# Vers_6_Moppy_Board.net
KiCad netlist of a schematic drawn in EAGLE
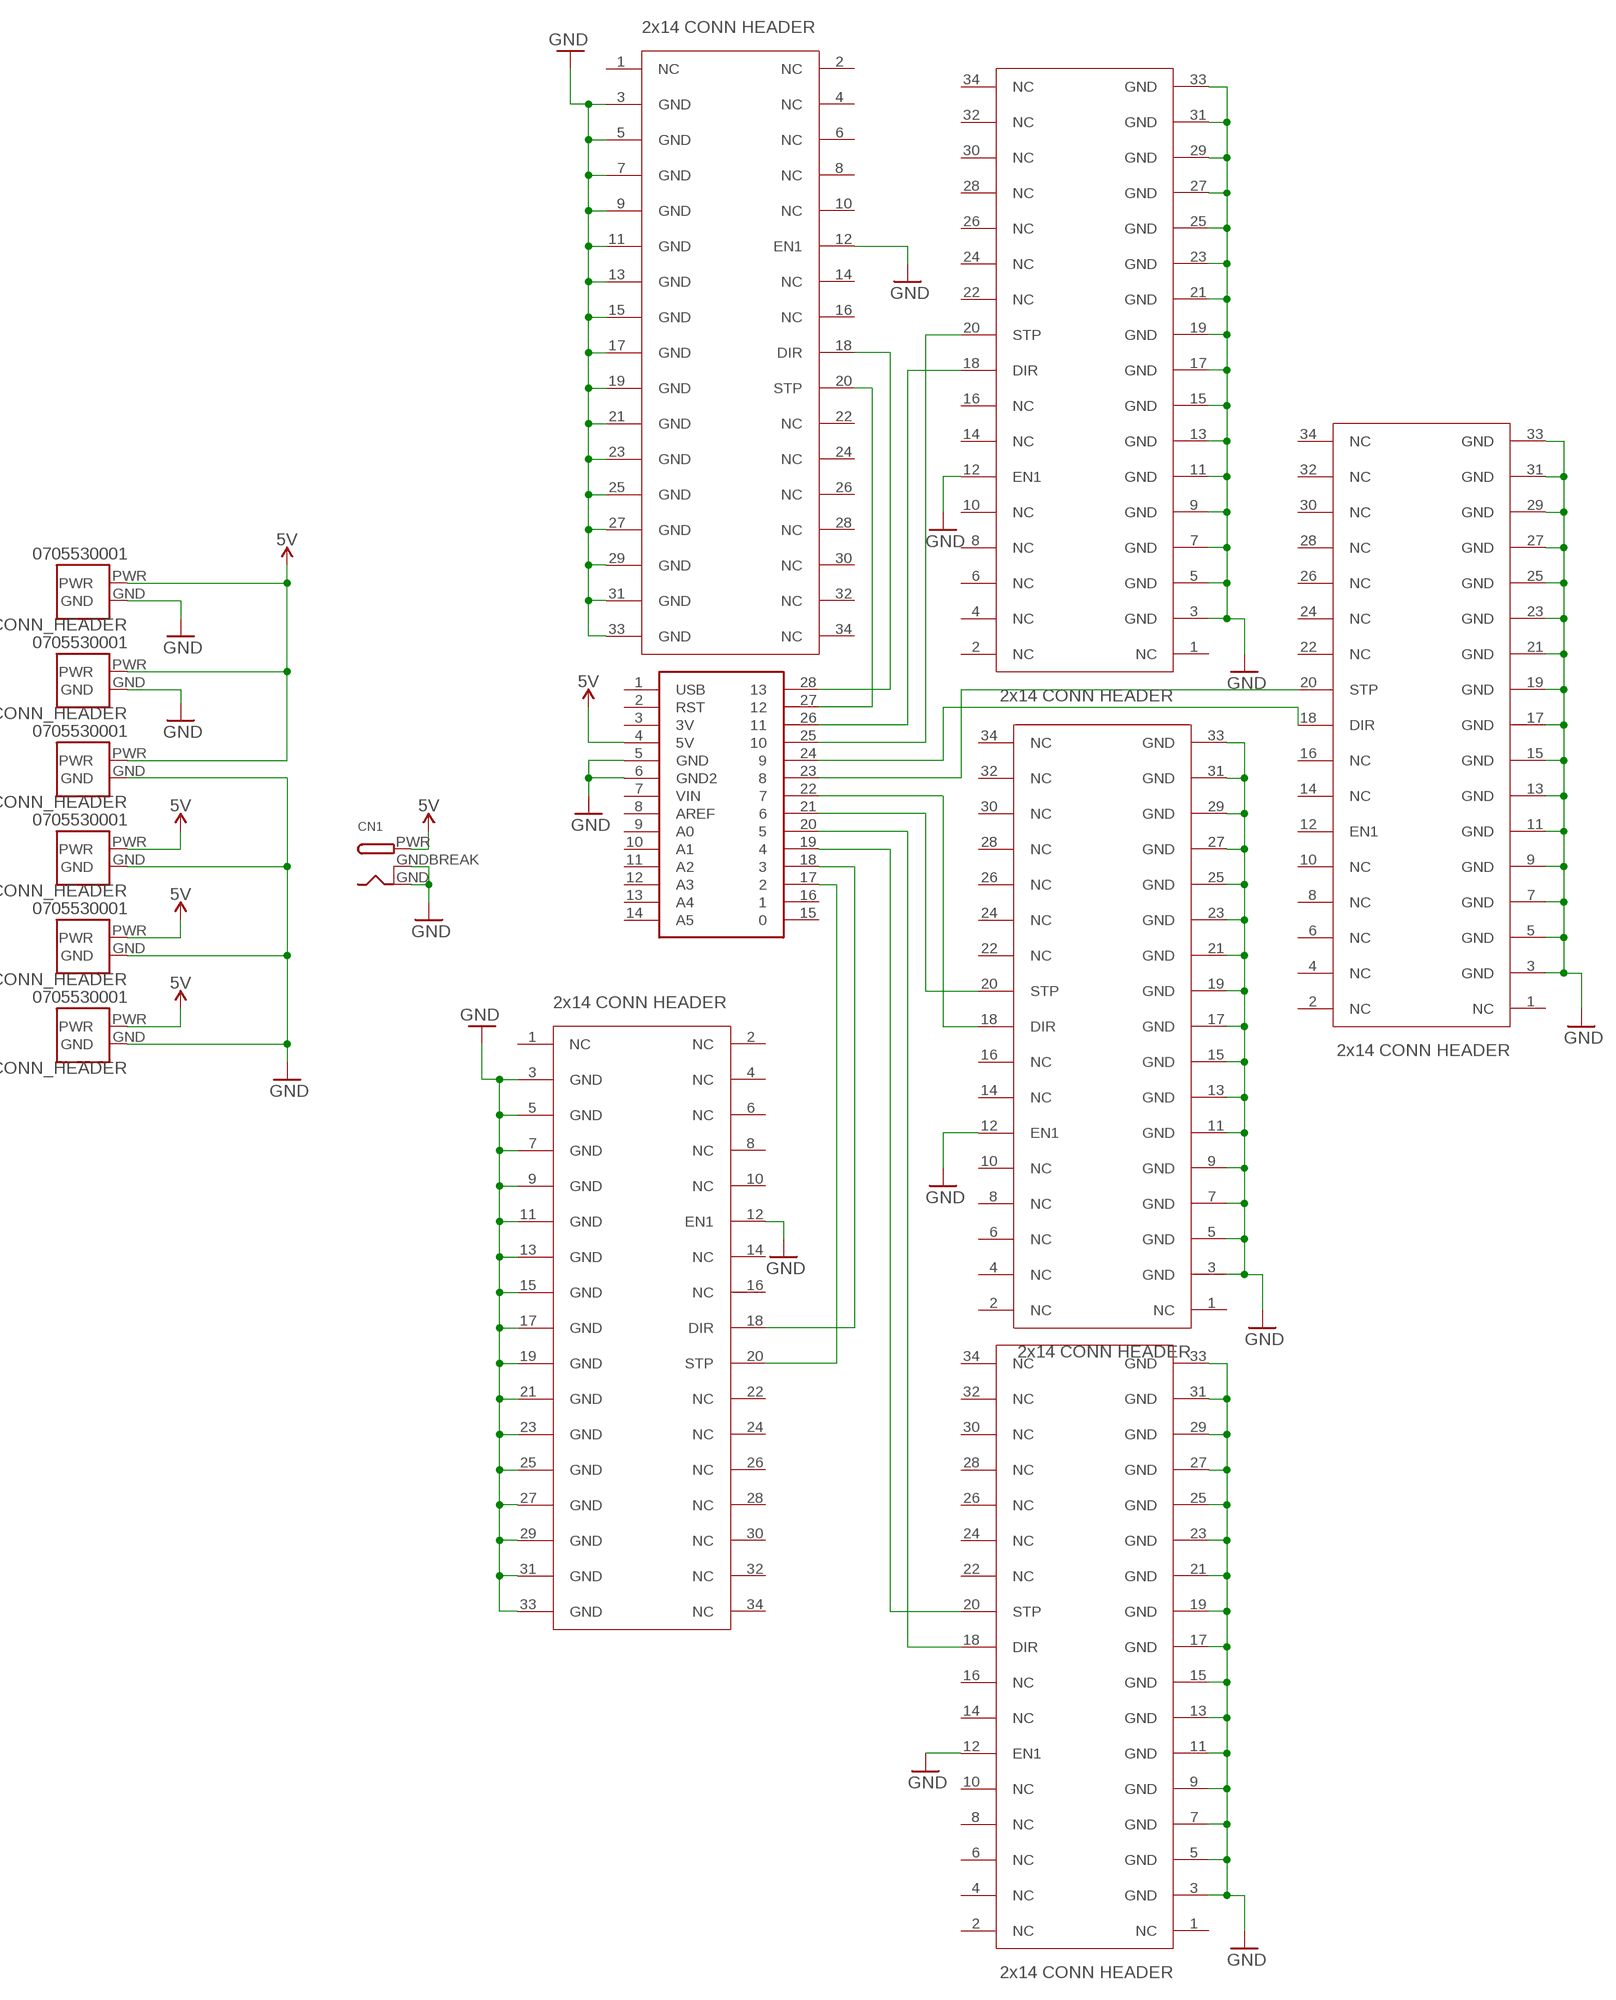
[diagram p0: schematic, sheet 1]

(export (version "E")
  (design (tool "Eeschema 10.0.6"))
  (components
    (comp (ref "CN1")
      (value "DCBARRELPTH")
      (footprint "eagle-import:DCJACK_2MM_PTH")
      (libsource (lib "eagle-import") (part "DCBARRELPTH"))
    )
    (comp (ref "U$1")
      (value "2X14_CONN_HEADER")
      (footprint "eagle-import:2X17_CONN_HEADER")
      (libsource (lib "eagle-import") (part "2X14_CONN_HEADER"))
    )
    (comp (ref "U$2")
      (value "2X14_CONN_HEADER")
      (footprint "eagle-import:2X17_CONN_HEADER")
      (libsource (lib "eagle-import") (part "2X14_CONN_HEADER"))
    )
    (comp (ref "U$3")
      (value "2X14_CONN_HEADER")
      (footprint "eagle-import:2X17_CONN_HEADER")
      (libsource (lib "eagle-import") (part "2X14_CONN_HEADER"))
    )
    (comp (ref "U$4")
      (value "2X14_CONN_HEADER")
      (footprint "eagle-import:2X17_CONN_HEADER")
      (libsource (lib "eagle-import") (part "2X14_CONN_HEADER"))
    )
    (comp (ref "U$5")
      (value "2X14_CONN_HEADER")
      (footprint "eagle-import:2X17_CONN_HEADER")
      (libsource (lib "eagle-import") (part "2X14_CONN_HEADER"))
    )
    (comp (ref "U$6")
      (value "2X14_CONN_HEADER")
      (footprint "eagle-import:2X17_CONN_HEADER")
      (libsource (lib "eagle-import") (part "2X14_CONN_HEADER"))
    )
    (comp (ref "U$8")
      (value "METROMINI")
      (footprint "eagle-import:METROMINI")
      (libsource (lib "eagle-import") (part "METROMINI"))
    )
    (comp (ref "X1")
      (value "0705530001")
      (footprint "eagle-import:MOLEX_0705530001")
      (fields (field (name "DIGI-KEY_PART_NUMBER") "WM4900-ND") (field (name "MF") "Molex"))
      (libsource (lib "eagle-import") (part "0705530001"))
    )
    (comp (ref "X2")
      (value "0705530001")
      (footprint "eagle-import:MOLEX_0705530001")
      (fields (field (name "DIGI-KEY_PART_NUMBER") "WM4900-ND") (field (name "MF") "Molex"))
      (libsource (lib "eagle-import") (part "0705530001"))
    )
    (comp (ref "X3")
      (value "0705530001")
      (footprint "eagle-import:MOLEX_0705530001")
      (fields (field (name "DIGI-KEY_PART_NUMBER") "WM4900-ND") (field (name "MF") "Molex"))
      (libsource (lib "eagle-import") (part "0705530001"))
    )
    (comp (ref "X4")
      (value "0705530001")
      (footprint "eagle-import:MOLEX_0705530001")
      (fields (field (name "DIGI-KEY_PART_NUMBER") "WM4900-ND") (field (name "MF") "Molex"))
      (libsource (lib "eagle-import") (part "0705530001"))
    )
    (comp (ref "X5")
      (value "0705530001")
      (footprint "eagle-import:MOLEX_0705530001")
      (fields (field (name "DIGI-KEY_PART_NUMBER") "WM4900-ND") (field (name "MF") "Molex"))
      (libsource (lib "eagle-import") (part "0705530001"))
    )
    (comp (ref "X6")
      (value "0705530001")
      (footprint "eagle-import:MOLEX_0705530001")
      (fields (field (name "DIGI-KEY_PART_NUMBER") "WM4900-ND") (field (name "MF") "Molex"))
      (libsource (lib "eagle-import") (part "0705530001"))
    )
  )
  (nets
    (net (code "1") (name "5V") (class "Default")
      (node (ref "CN1") (pin "PWR") (pinfunction "PWR_PWR") (pintype "power_in"))
      (node (ref "U$8") (pin "4") (pinfunction "5V_4") (pintype "bidirectional"))
      (node (ref "X1") (pin "PWR") (pinfunction "PWR_PWR") (pintype "passive"))
      (node (ref "X2") (pin "PWR") (pinfunction "PWR_PWR") (pintype "passive"))
      (node (ref "X3") (pin "PWR") (pinfunction "PWR_PWR") (pintype "passive"))
      (node (ref "X4") (pin "PWR") (pinfunction "PWR_PWR") (pintype "passive"))
      (node (ref "X5") (pin "PWR") (pinfunction "PWR_PWR") (pintype "passive"))
      (node (ref "X6") (pin "PWR") (pinfunction "PWR_PWR") (pintype "passive"))
    )
    (net (code "2") (name "GND") (class "Default")
      (node (ref "CN1") (pin "GND") (pinfunction "GND_GND") (pintype "power_in"))
      (node (ref "CN1") (pin "GNDBREAK") (pinfunction "GNDBREAK_GNDBREAK") (pintype "power_in"))
      (node (ref "U$1") (pin "11") (pinfunction "GND_11") (pintype "bidirectional"))
      (node (ref "U$1") (pin "12") (pinfunction "EN1_12") (pintype "bidirectional"))
      (node (ref "U$1") (pin "13") (pinfunction "GND_13") (pintype "bidirectional"))
      (node (ref "U$1") (pin "15") (pinfunction "GND_15") (pintype "bidirectional"))
      (node (ref "U$1") (pin "17") (pinfunction "GND_17") (pintype "bidirectional"))
      (node (ref "U$1") (pin "19") (pinfunction "GND_19") (pintype "bidirectional"))
      (node (ref "U$1") (pin "21") (pinfunction "GND_21") (pintype "bidirectional"))
      (node (ref "U$1") (pin "23") (pinfunction "GND_23") (pintype "bidirectional"))
      (node (ref "U$1") (pin "25") (pinfunction "GND_25") (pintype "bidirectional"))
      (node (ref "U$1") (pin "27") (pinfunction "GND_27") (pintype "bidirectional"))
      (node (ref "U$1") (pin "29") (pinfunction "GND_29") (pintype "bidirectional"))
      (node (ref "U$1") (pin "3") (pinfunction "GND_3") (pintype "bidirectional"))
      (node (ref "U$1") (pin "31") (pinfunction "GND_31") (pintype "bidirectional"))
      (node (ref "U$1") (pin "33") (pinfunction "GND_33") (pintype "bidirectional"))
      (node (ref "U$1") (pin "5") (pinfunction "GND_5") (pintype "bidirectional"))
      (node (ref "U$1") (pin "7") (pinfunction "GND_7") (pintype "bidirectional"))
      (node (ref "U$1") (pin "9") (pinfunction "GND_9") (pintype "bidirectional"))
      (node (ref "U$2") (pin "11") (pinfunction "GND_11") (pintype "bidirectional"))
      (node (ref "U$2") (pin "12") (pinfunction "EN1_12") (pintype "bidirectional"))
      (node (ref "U$2") (pin "13") (pinfunction "GND_13") (pintype "bidirectional"))
      (node (ref "U$2") (pin "15") (pinfunction "GND_15") (pintype "bidirectional"))
      (node (ref "U$2") (pin "17") (pinfunction "GND_17") (pintype "bidirectional"))
      (node (ref "U$2") (pin "19") (pinfunction "GND_19") (pintype "bidirectional"))
      (node (ref "U$2") (pin "21") (pinfunction "GND_21") (pintype "bidirectional"))
      (node (ref "U$2") (pin "23") (pinfunction "GND_23") (pintype "bidirectional"))
      (node (ref "U$2") (pin "25") (pinfunction "GND_25") (pintype "bidirectional"))
      (node (ref "U$2") (pin "27") (pinfunction "GND_27") (pintype "bidirectional"))
      (node (ref "U$2") (pin "29") (pinfunction "GND_29") (pintype "bidirectional"))
      (node (ref "U$2") (pin "3") (pinfunction "GND_3") (pintype "bidirectional"))
      (node (ref "U$2") (pin "31") (pinfunction "GND_31") (pintype "bidirectional"))
      (node (ref "U$2") (pin "33") (pinfunction "GND_33") (pintype "bidirectional"))
      (node (ref "U$2") (pin "5") (pinfunction "GND_5") (pintype "bidirectional"))
      (node (ref "U$2") (pin "7") (pinfunction "GND_7") (pintype "bidirectional"))
      (node (ref "U$2") (pin "9") (pinfunction "GND_9") (pintype "bidirectional"))
      (node (ref "U$3") (pin "11") (pinfunction "GND_11") (pintype "bidirectional"))
      (node (ref "U$3") (pin "12") (pinfunction "EN1_12") (pintype "bidirectional"))
      (node (ref "U$3") (pin "13") (pinfunction "GND_13") (pintype "bidirectional"))
      (node (ref "U$3") (pin "15") (pinfunction "GND_15") (pintype "bidirectional"))
      (node (ref "U$3") (pin "17") (pinfunction "GND_17") (pintype "bidirectional"))
      (node (ref "U$3") (pin "19") (pinfunction "GND_19") (pintype "bidirectional"))
      (node (ref "U$3") (pin "21") (pinfunction "GND_21") (pintype "bidirectional"))
      (node (ref "U$3") (pin "23") (pinfunction "GND_23") (pintype "bidirectional"))
      (node (ref "U$3") (pin "25") (pinfunction "GND_25") (pintype "bidirectional"))
      (node (ref "U$3") (pin "27") (pinfunction "GND_27") (pintype "bidirectional"))
      (node (ref "U$3") (pin "29") (pinfunction "GND_29") (pintype "bidirectional"))
      (node (ref "U$3") (pin "3") (pinfunction "GND_3") (pintype "bidirectional"))
      (node (ref "U$3") (pin "31") (pinfunction "GND_31") (pintype "bidirectional"))
      (node (ref "U$3") (pin "33") (pinfunction "GND_33") (pintype "bidirectional"))
      (node (ref "U$3") (pin "5") (pinfunction "GND_5") (pintype "bidirectional"))
      (node (ref "U$3") (pin "7") (pinfunction "GND_7") (pintype "bidirectional"))
      (node (ref "U$3") (pin "9") (pinfunction "GND_9") (pintype "bidirectional"))
      (node (ref "U$4") (pin "11") (pinfunction "GND_11") (pintype "bidirectional"))
      (node (ref "U$4") (pin "12") (pinfunction "EN1_12") (pintype "bidirectional"))
      (node (ref "U$4") (pin "13") (pinfunction "GND_13") (pintype "bidirectional"))
      (node (ref "U$4") (pin "15") (pinfunction "GND_15") (pintype "bidirectional"))
      (node (ref "U$4") (pin "17") (pinfunction "GND_17") (pintype "bidirectional"))
      (node (ref "U$4") (pin "19") (pinfunction "GND_19") (pintype "bidirectional"))
      (node (ref "U$4") (pin "21") (pinfunction "GND_21") (pintype "bidirectional"))
      (node (ref "U$4") (pin "23") (pinfunction "GND_23") (pintype "bidirectional"))
      (node (ref "U$4") (pin "25") (pinfunction "GND_25") (pintype "bidirectional"))
      (node (ref "U$4") (pin "27") (pinfunction "GND_27") (pintype "bidirectional"))
      (node (ref "U$4") (pin "29") (pinfunction "GND_29") (pintype "bidirectional"))
      (node (ref "U$4") (pin "3") (pinfunction "GND_3") (pintype "bidirectional"))
      (node (ref "U$4") (pin "31") (pinfunction "GND_31") (pintype "bidirectional"))
      (node (ref "U$4") (pin "33") (pinfunction "GND_33") (pintype "bidirectional"))
      (node (ref "U$4") (pin "5") (pinfunction "GND_5") (pintype "bidirectional"))
      (node (ref "U$4") (pin "7") (pinfunction "GND_7") (pintype "bidirectional"))
      (node (ref "U$4") (pin "9") (pinfunction "GND_9") (pintype "bidirectional"))
      (node (ref "U$5") (pin "11") (pinfunction "GND_11") (pintype "bidirectional"))
      (node (ref "U$5") (pin "12") (pinfunction "EN1_12") (pintype "bidirectional"))
      (node (ref "U$5") (pin "13") (pinfunction "GND_13") (pintype "bidirectional"))
      (node (ref "U$5") (pin "15") (pinfunction "GND_15") (pintype "bidirectional"))
      (node (ref "U$5") (pin "17") (pinfunction "GND_17") (pintype "bidirectional"))
      (node (ref "U$5") (pin "19") (pinfunction "GND_19") (pintype "bidirectional"))
      (node (ref "U$5") (pin "21") (pinfunction "GND_21") (pintype "bidirectional"))
      (node (ref "U$5") (pin "23") (pinfunction "GND_23") (pintype "bidirectional"))
      (node (ref "U$5") (pin "25") (pinfunction "GND_25") (pintype "bidirectional"))
      (node (ref "U$5") (pin "27") (pinfunction "GND_27") (pintype "bidirectional"))
      (node (ref "U$5") (pin "29") (pinfunction "GND_29") (pintype "bidirectional"))
      (node (ref "U$5") (pin "3") (pinfunction "GND_3") (pintype "bidirectional"))
      (node (ref "U$5") (pin "31") (pinfunction "GND_31") (pintype "bidirectional"))
      (node (ref "U$5") (pin "33") (pinfunction "GND_33") (pintype "bidirectional"))
      (node (ref "U$5") (pin "5") (pinfunction "GND_5") (pintype "bidirectional"))
      (node (ref "U$5") (pin "7") (pinfunction "GND_7") (pintype "bidirectional"))
      (node (ref "U$5") (pin "9") (pinfunction "GND_9") (pintype "bidirectional"))
      (node (ref "U$6") (pin "11") (pinfunction "GND_11") (pintype "bidirectional"))
      (node (ref "U$6") (pin "13") (pinfunction "GND_13") (pintype "bidirectional"))
      (node (ref "U$6") (pin "15") (pinfunction "GND_15") (pintype "bidirectional"))
      (node (ref "U$6") (pin "17") (pinfunction "GND_17") (pintype "bidirectional"))
      (node (ref "U$6") (pin "19") (pinfunction "GND_19") (pintype "bidirectional"))
      (node (ref "U$6") (pin "21") (pinfunction "GND_21") (pintype "bidirectional"))
      (node (ref "U$6") (pin "23") (pinfunction "GND_23") (pintype "bidirectional"))
      (node (ref "U$6") (pin "25") (pinfunction "GND_25") (pintype "bidirectional"))
      (node (ref "U$6") (pin "27") (pinfunction "GND_27") (pintype "bidirectional"))
      (node (ref "U$6") (pin "29") (pinfunction "GND_29") (pintype "bidirectional"))
      (node (ref "U$6") (pin "3") (pinfunction "GND_3") (pintype "bidirectional"))
      (node (ref "U$6") (pin "31") (pinfunction "GND_31") (pintype "bidirectional"))
      (node (ref "U$6") (pin "33") (pinfunction "GND_33") (pintype "bidirectional"))
      (node (ref "U$6") (pin "5") (pinfunction "GND_5") (pintype "bidirectional"))
      (node (ref "U$6") (pin "7") (pinfunction "GND_7") (pintype "bidirectional"))
      (node (ref "U$6") (pin "9") (pinfunction "GND_9") (pintype "bidirectional"))
      (node (ref "U$8") (pin "5") (pinfunction "GND_5") (pintype "bidirectional"))
      (node (ref "U$8") (pin "6") (pinfunction "GND2_6") (pintype "bidirectional"))
      (node (ref "X1") (pin "GND") (pinfunction "GND_GND") (pintype "passive"))
      (node (ref "X2") (pin "GND") (pinfunction "GND_GND") (pintype "passive"))
      (node (ref "X3") (pin "GND") (pinfunction "GND_GND") (pintype "passive"))
      (node (ref "X4") (pin "GND") (pinfunction "GND_GND") (pintype "passive"))
      (node (ref "X5") (pin "GND") (pinfunction "GND_GND") (pintype "passive"))
      (node (ref "X6") (pin "GND") (pinfunction "GND_GND") (pintype "passive"))
    )
    (net (code "3") (name "Net-(U$1-DIR)") (class "Default")
      (node (ref "U$1") (pin "18") (pinfunction "DIR_18") (pintype "bidirectional"))
      (node (ref "U$8") (pin "18") (pinfunction "3_18") (pintype "bidirectional"))
    )
    (net (code "4") (name "Net-(U$1-STP)") (class "Default")
      (node (ref "U$1") (pin "20") (pinfunction "STP_20") (pintype "bidirectional"))
      (node (ref "U$8") (pin "17") (pinfunction "2_17") (pintype "bidirectional"))
    )
    (net (code "5") (name "Net-(U$2-DIR)") (class "Default")
      (node (ref "U$2") (pin "18") (pinfunction "DIR_18") (pintype "bidirectional"))
      (node (ref "U$8") (pin "28") (pinfunction "13_28") (pintype "bidirectional"))
    )
    (net (code "6") (name "Net-(U$2-STP)") (class "Default")
      (node (ref "U$2") (pin "20") (pinfunction "STP_20") (pintype "bidirectional"))
      (node (ref "U$8") (pin "27") (pinfunction "12_27") (pintype "bidirectional"))
    )
    (net (code "7") (name "Net-(U$3-DIR)") (class "Default")
      (node (ref "U$3") (pin "18") (pinfunction "DIR_18") (pintype "bidirectional"))
      (node (ref "U$8") (pin "26") (pinfunction "11_26") (pintype "bidirectional"))
    )
    (net (code "8") (name "Net-(U$3-STP)") (class "Default")
      (node (ref "U$3") (pin "20") (pinfunction "STP_20") (pintype "bidirectional"))
      (node (ref "U$8") (pin "25") (pinfunction "10_25") (pintype "bidirectional"))
    )
    (net (code "9") (name "Net-(U$4-DIR)") (class "Default")
      (node (ref "U$4") (pin "18") (pinfunction "DIR_18") (pintype "bidirectional"))
      (node (ref "U$8") (pin "20") (pinfunction "5_20") (pintype "bidirectional"))
    )
    (net (code "10") (name "Net-(U$4-STP)") (class "Default")
      (node (ref "U$4") (pin "20") (pinfunction "STP_20") (pintype "bidirectional"))
      (node (ref "U$8") (pin "19") (pinfunction "4_19") (pintype "bidirectional"))
    )
    (net (code "11") (name "Net-(U$5-DIR)") (class "Default")
      (node (ref "U$5") (pin "18") (pinfunction "DIR_18") (pintype "bidirectional"))
      (node (ref "U$8") (pin "22") (pinfunction "7_22") (pintype "bidirectional"))
    )
    (net (code "12") (name "Net-(U$5-STP)") (class "Default")
      (node (ref "U$5") (pin "20") (pinfunction "STP_20") (pintype "bidirectional"))
      (node (ref "U$8") (pin "21") (pinfunction "6_21") (pintype "bidirectional"))
    )
    (net (code "13") (name "Net-(U$6-DIR)") (class "Default")
      (node (ref "U$6") (pin "18") (pinfunction "DIR_18") (pintype "bidirectional"))
      (node (ref "U$8") (pin "24") (pinfunction "9_24") (pintype "bidirectional"))
    )
    (net (code "14") (name "Net-(U$6-STP)") (class "Default")
      (node (ref "U$6") (pin "20") (pinfunction "STP_20") (pintype "bidirectional"))
      (node (ref "U$8") (pin "23") (pinfunction "8_23") (pintype "bidirectional"))
    )
    (net (code "15") (name "unconnected-(U$1-NC-Pad1)") (class "Default")
      (node (ref "U$1") (pin "1") (pinfunction "NC_1") (pintype "bidirectional"))
    )
    (net (code "16") (name "unconnected-(U$1-NC-Pad2)") (class "Default")
      (node (ref "U$1") (pin "2") (pinfunction "NC_2") (pintype "bidirectional"))
    )
    (net (code "17") (name "unconnected-(U$1-NC-Pad4)") (class "Default")
      (node (ref "U$1") (pin "4") (pinfunction "NC_4") (pintype "bidirectional"))
    )
    (net (code "18") (name "unconnected-(U$1-NC-Pad6)") (class "Default")
      (node (ref "U$1") (pin "6") (pinfunction "NC_6") (pintype "bidirectional"))
    )
    (net (code "19") (name "unconnected-(U$1-NC-Pad8)") (class "Default")
      (node (ref "U$1") (pin "8") (pinfunction "NC_8") (pintype "bidirectional"))
    )
    (net (code "20") (name "unconnected-(U$1-NC-Pad10)") (class "Default")
      (node (ref "U$1") (pin "10") (pinfunction "NC_10") (pintype "bidirectional"))
    )
    (net (code "21") (name "unconnected-(U$1-NC-Pad14)") (class "Default")
      (node (ref "U$1") (pin "14") (pinfunction "NC_14") (pintype "bidirectional"))
    )
    (net (code "22") (name "unconnected-(U$1-NC-Pad16)") (class "Default")
      (node (ref "U$1") (pin "16") (pinfunction "NC_16") (pintype "bidirectional"))
    )
    (net (code "23") (name "unconnected-(U$1-NC-Pad22)") (class "Default")
      (node (ref "U$1") (pin "22") (pinfunction "NC_22") (pintype "bidirectional"))
    )
    (net (code "24") (name "unconnected-(U$1-NC-Pad24)") (class "Default")
      (node (ref "U$1") (pin "24") (pinfunction "NC_24") (pintype "bidirectional"))
    )
    (net (code "25") (name "unconnected-(U$1-NC-Pad26)") (class "Default")
      (node (ref "U$1") (pin "26") (pinfunction "NC_26") (pintype "bidirectional"))
    )
    (net (code "26") (name "unconnected-(U$1-NC-Pad28)") (class "Default")
      (node (ref "U$1") (pin "28") (pinfunction "NC_28") (pintype "bidirectional"))
    )
    (net (code "27") (name "unconnected-(U$1-NC-Pad30)") (class "Default")
      (node (ref "U$1") (pin "30") (pinfunction "NC_30") (pintype "bidirectional"))
    )
    (net (code "28") (name "unconnected-(U$1-NC-Pad32)") (class "Default")
      (node (ref "U$1") (pin "32") (pinfunction "NC_32") (pintype "bidirectional"))
    )
    (net (code "29") (name "unconnected-(U$1-NC-Pad34)") (class "Default")
      (node (ref "U$1") (pin "34") (pinfunction "NC_34") (pintype "bidirectional"))
    )
    (net (code "30") (name "unconnected-(U$2-NC-Pad1)") (class "Default")
      (node (ref "U$2") (pin "1") (pinfunction "NC_1") (pintype "bidirectional"))
    )
    (net (code "31") (name "unconnected-(U$2-NC-Pad2)") (class "Default")
      (node (ref "U$2") (pin "2") (pinfunction "NC_2") (pintype "bidirectional"))
    )
    (net (code "32") (name "unconnected-(U$2-NC-Pad4)") (class "Default")
      (node (ref "U$2") (pin "4") (pinfunction "NC_4") (pintype "bidirectional"))
    )
    (net (code "33") (name "unconnected-(U$2-NC-Pad6)") (class "Default")
      (node (ref "U$2") (pin "6") (pinfunction "NC_6") (pintype "bidirectional"))
    )
    (net (code "34") (name "unconnected-(U$2-NC-Pad8)") (class "Default")
      (node (ref "U$2") (pin "8") (pinfunction "NC_8") (pintype "bidirectional"))
    )
    (net (code "35") (name "unconnected-(U$2-NC-Pad10)") (class "Default")
      (node (ref "U$2") (pin "10") (pinfunction "NC_10") (pintype "bidirectional"))
    )
    (net (code "36") (name "unconnected-(U$2-NC-Pad14)") (class "Default")
      (node (ref "U$2") (pin "14") (pinfunction "NC_14") (pintype "bidirectional"))
    )
    (net (code "37") (name "unconnected-(U$2-NC-Pad16)") (class "Default")
      (node (ref "U$2") (pin "16") (pinfunction "NC_16") (pintype "bidirectional"))
    )
    (net (code "38") (name "unconnected-(U$2-NC-Pad22)") (class "Default")
      (node (ref "U$2") (pin "22") (pinfunction "NC_22") (pintype "bidirectional"))
    )
    (net (code "39") (name "unconnected-(U$2-NC-Pad24)") (class "Default")
      (node (ref "U$2") (pin "24") (pinfunction "NC_24") (pintype "bidirectional"))
    )
    (net (code "40") (name "unconnected-(U$2-NC-Pad26)") (class "Default")
      (node (ref "U$2") (pin "26") (pinfunction "NC_26") (pintype "bidirectional"))
    )
    (net (code "41") (name "unconnected-(U$2-NC-Pad28)") (class "Default")
      (node (ref "U$2") (pin "28") (pinfunction "NC_28") (pintype "bidirectional"))
    )
    (net (code "42") (name "unconnected-(U$2-NC-Pad30)") (class "Default")
      (node (ref "U$2") (pin "30") (pinfunction "NC_30") (pintype "bidirectional"))
    )
    (net (code "43") (name "unconnected-(U$2-NC-Pad32)") (class "Default")
      (node (ref "U$2") (pin "32") (pinfunction "NC_32") (pintype "bidirectional"))
    )
    (net (code "44") (name "unconnected-(U$2-NC-Pad34)") (class "Default")
      (node (ref "U$2") (pin "34") (pinfunction "NC_34") (pintype "bidirectional"))
    )
    (net (code "45") (name "unconnected-(U$3-NC-Pad1)") (class "Default")
      (node (ref "U$3") (pin "1") (pinfunction "NC_1") (pintype "bidirectional"))
    )
    (net (code "46") (name "unconnected-(U$3-NC-Pad2)") (class "Default")
      (node (ref "U$3") (pin "2") (pinfunction "NC_2") (pintype "bidirectional"))
    )
    (net (code "47") (name "unconnected-(U$3-NC-Pad4)") (class "Default")
      (node (ref "U$3") (pin "4") (pinfunction "NC_4") (pintype "bidirectional"))
    )
    (net (code "48") (name "unconnected-(U$3-NC-Pad6)") (class "Default")
      (node (ref "U$3") (pin "6") (pinfunction "NC_6") (pintype "bidirectional"))
    )
    (net (code "49") (name "unconnected-(U$3-NC-Pad8)") (class "Default")
      (node (ref "U$3") (pin "8") (pinfunction "NC_8") (pintype "bidirectional"))
    )
    (net (code "50") (name "unconnected-(U$3-NC-Pad10)") (class "Default")
      (node (ref "U$3") (pin "10") (pinfunction "NC_10") (pintype "bidirectional"))
    )
    (net (code "51") (name "unconnected-(U$3-NC-Pad14)") (class "Default")
      (node (ref "U$3") (pin "14") (pinfunction "NC_14") (pintype "bidirectional"))
    )
    (net (code "52") (name "unconnected-(U$3-NC-Pad16)") (class "Default")
      (node (ref "U$3") (pin "16") (pinfunction "NC_16") (pintype "bidirectional"))
    )
    (net (code "53") (name "unconnected-(U$3-NC-Pad22)") (class "Default")
      (node (ref "U$3") (pin "22") (pinfunction "NC_22") (pintype "bidirectional"))
    )
    (net (code "54") (name "unconnected-(U$3-NC-Pad24)") (class "Default")
      (node (ref "U$3") (pin "24") (pinfunction "NC_24") (pintype "bidirectional"))
    )
    (net (code "55") (name "unconnected-(U$3-NC-Pad26)") (class "Default")
      (node (ref "U$3") (pin "26") (pinfunction "NC_26") (pintype "bidirectional"))
    )
    (net (code "56") (name "unconnected-(U$3-NC-Pad28)") (class "Default")
      (node (ref "U$3") (pin "28") (pinfunction "NC_28") (pintype "bidirectional"))
    )
    (net (code "57") (name "unconnected-(U$3-NC-Pad30)") (class "Default")
      (node (ref "U$3") (pin "30") (pinfunction "NC_30") (pintype "bidirectional"))
    )
    (net (code "58") (name "unconnected-(U$3-NC-Pad32)") (class "Default")
      (node (ref "U$3") (pin "32") (pinfunction "NC_32") (pintype "bidirectional"))
    )
    (net (code "59") (name "unconnected-(U$3-NC-Pad34)") (class "Default")
      (node (ref "U$3") (pin "34") (pinfunction "NC_34") (pintype "bidirectional"))
    )
    (net (code "60") (name "unconnected-(U$4-NC-Pad1)") (class "Default")
      (node (ref "U$4") (pin "1") (pinfunction "NC_1") (pintype "bidirectional"))
    )
    (net (code "61") (name "unconnected-(U$4-NC-Pad2)") (class "Default")
      (node (ref "U$4") (pin "2") (pinfunction "NC_2") (pintype "bidirectional"))
    )
    (net (code "62") (name "unconnected-(U$4-NC-Pad4)") (class "Default")
      (node (ref "U$4") (pin "4") (pinfunction "NC_4") (pintype "bidirectional"))
    )
    (net (code "63") (name "unconnected-(U$4-NC-Pad6)") (class "Default")
      (node (ref "U$4") (pin "6") (pinfunction "NC_6") (pintype "bidirectional"))
    )
    (net (code "64") (name "unconnected-(U$4-NC-Pad8)") (class "Default")
      (node (ref "U$4") (pin "8") (pinfunction "NC_8") (pintype "bidirectional"))
    )
    (net (code "65") (name "unconnected-(U$4-NC-Pad10)") (class "Default")
      (node (ref "U$4") (pin "10") (pinfunction "NC_10") (pintype "bidirectional"))
    )
    (net (code "66") (name "unconnected-(U$4-NC-Pad14)") (class "Default")
      (node (ref "U$4") (pin "14") (pinfunction "NC_14") (pintype "bidirectional"))
    )
    (net (code "67") (name "unconnected-(U$4-NC-Pad16)") (class "Default")
      (node (ref "U$4") (pin "16") (pinfunction "NC_16") (pintype "bidirectional"))
    )
    (net (code "68") (name "unconnected-(U$4-NC-Pad22)") (class "Default")
      (node (ref "U$4") (pin "22") (pinfunction "NC_22") (pintype "bidirectional"))
    )
    (net (code "69") (name "unconnected-(U$4-NC-Pad24)") (class "Default")
      (node (ref "U$4") (pin "24") (pinfunction "NC_24") (pintype "bidirectional"))
    )
    (net (code "70") (name "unconnected-(U$4-NC-Pad26)") (class "Default")
      (node (ref "U$4") (pin "26") (pinfunction "NC_26") (pintype "bidirectional"))
    )
    (net (code "71") (name "unconnected-(U$4-NC-Pad28)") (class "Default")
      (node (ref "U$4") (pin "28") (pinfunction "NC_28") (pintype "bidirectional"))
    )
    (net (code "72") (name "unconnected-(U$4-NC-Pad30)") (class "Default")
      (node (ref "U$4") (pin "30") (pinfunction "NC_30") (pintype "bidirectional"))
    )
    (net (code "73") (name "unconnected-(U$4-NC-Pad32)") (class "Default")
      (node (ref "U$4") (pin "32") (pinfunction "NC_32") (pintype "bidirectional"))
    )
    (net (code "74") (name "unconnected-(U$4-NC-Pad34)") (class "Default")
      (node (ref "U$4") (pin "34") (pinfunction "NC_34") (pintype "bidirectional"))
    )
    (net (code "75") (name "unconnected-(U$5-NC-Pad1)") (class "Default")
      (node (ref "U$5") (pin "1") (pinfunction "NC_1") (pintype "bidirectional"))
    )
    (net (code "76") (name "unconnected-(U$5-NC-Pad2)") (class "Default")
      (node (ref "U$5") (pin "2") (pinfunction "NC_2") (pintype "bidirectional"))
    )
    (net (code "77") (name "unconnected-(U$5-NC-Pad4)") (class "Default")
      (node (ref "U$5") (pin "4") (pinfunction "NC_4") (pintype "bidirectional"))
    )
    (net (code "78") (name "unconnected-(U$5-NC-Pad6)") (class "Default")
      (node (ref "U$5") (pin "6") (pinfunction "NC_6") (pintype "bidirectional"))
    )
    (net (code "79") (name "unconnected-(U$5-NC-Pad8)") (class "Default")
      (node (ref "U$5") (pin "8") (pinfunction "NC_8") (pintype "bidirectional"))
    )
    (net (code "80") (name "unconnected-(U$5-NC-Pad10)") (class "Default")
      (node (ref "U$5") (pin "10") (pinfunction "NC_10") (pintype "bidirectional"))
    )
    (net (code "81") (name "unconnected-(U$5-NC-Pad14)") (class "Default")
      (node (ref "U$5") (pin "14") (pinfunction "NC_14") (pintype "bidirectional"))
    )
    (net (code "82") (name "unconnected-(U$5-NC-Pad16)") (class "Default")
      (node (ref "U$5") (pin "16") (pinfunction "NC_16") (pintype "bidirectional"))
    )
    (net (code "83") (name "unconnected-(U$5-NC-Pad22)") (class "Default")
      (node (ref "U$5") (pin "22") (pinfunction "NC_22") (pintype "bidirectional"))
    )
    (net (code "84") (name "unconnected-(U$5-NC-Pad24)") (class "Default")
      (node (ref "U$5") (pin "24") (pinfunction "NC_24") (pintype "bidirectional"))
    )
    (net (code "85") (name "unconnected-(U$5-NC-Pad26)") (class "Default")
      (node (ref "U$5") (pin "26") (pinfunction "NC_26") (pintype "bidirectional"))
    )
    (net (code "86") (name "unconnected-(U$5-NC-Pad28)") (class "Default")
      (node (ref "U$5") (pin "28") (pinfunction "NC_28") (pintype "bidirectional"))
    )
    (net (code "87") (name "unconnected-(U$5-NC-Pad30)") (class "Default")
      (node (ref "U$5") (pin "30") (pinfunction "NC_30") (pintype "bidirectional"))
    )
    (net (code "88") (name "unconnected-(U$5-NC-Pad32)") (class "Default")
      (node (ref "U$5") (pin "32") (pinfunction "NC_32") (pintype "bidirectional"))
    )
    (net (code "89") (name "unconnected-(U$5-NC-Pad34)") (class "Default")
      (node (ref "U$5") (pin "34") (pinfunction "NC_34") (pintype "bidirectional"))
    )
    (net (code "90") (name "unconnected-(U$6-EN1-Pad12)") (class "Default")
      (node (ref "U$6") (pin "12") (pinfunction "EN1_12") (pintype "bidirectional"))
    )
    (net (code "91") (name "unconnected-(U$6-NC-Pad1)") (class "Default")
      (node (ref "U$6") (pin "1") (pinfunction "NC_1") (pintype "bidirectional"))
    )
    (net (code "92") (name "unconnected-(U$6-NC-Pad2)") (class "Default")
      (node (ref "U$6") (pin "2") (pinfunction "NC_2") (pintype "bidirectional"))
    )
    (net (code "93") (name "unconnected-(U$6-NC-Pad4)") (class "Default")
      (node (ref "U$6") (pin "4") (pinfunction "NC_4") (pintype "bidirectional"))
    )
    (net (code "94") (name "unconnected-(U$6-NC-Pad6)") (class "Default")
      (node (ref "U$6") (pin "6") (pinfunction "NC_6") (pintype "bidirectional"))
    )
    (net (code "95") (name "unconnected-(U$6-NC-Pad8)") (class "Default")
      (node (ref "U$6") (pin "8") (pinfunction "NC_8") (pintype "bidirectional"))
    )
    (net (code "96") (name "unconnected-(U$6-NC-Pad10)") (class "Default")
      (node (ref "U$6") (pin "10") (pinfunction "NC_10") (pintype "bidirectional"))
    )
    (net (code "97") (name "unconnected-(U$6-NC-Pad14)") (class "Default")
      (node (ref "U$6") (pin "14") (pinfunction "NC_14") (pintype "bidirectional"))
    )
    (net (code "98") (name "unconnected-(U$6-NC-Pad16)") (class "Default")
      (node (ref "U$6") (pin "16") (pinfunction "NC_16") (pintype "bidirectional"))
    )
    (net (code "99") (name "unconnected-(U$6-NC-Pad22)") (class "Default")
      (node (ref "U$6") (pin "22") (pinfunction "NC_22") (pintype "bidirectional"))
    )
    (net (code "100") (name "unconnected-(U$6-NC-Pad24)") (class "Default")
      (node (ref "U$6") (pin "24") (pinfunction "NC_24") (pintype "bidirectional"))
    )
    (net (code "101") (name "unconnected-(U$6-NC-Pad26)") (class "Default")
      (node (ref "U$6") (pin "26") (pinfunction "NC_26") (pintype "bidirectional"))
    )
    (net (code "102") (name "unconnected-(U$6-NC-Pad28)") (class "Default")
      (node (ref "U$6") (pin "28") (pinfunction "NC_28") (pintype "bidirectional"))
    )
    (net (code "103") (name "unconnected-(U$6-NC-Pad30)") (class "Default")
      (node (ref "U$6") (pin "30") (pinfunction "NC_30") (pintype "bidirectional"))
    )
    (net (code "104") (name "unconnected-(U$6-NC-Pad32)") (class "Default")
      (node (ref "U$6") (pin "32") (pinfunction "NC_32") (pintype "bidirectional"))
    )
    (net (code "105") (name "unconnected-(U$6-NC-Pad34)") (class "Default")
      (node (ref "U$6") (pin "34") (pinfunction "NC_34") (pintype "bidirectional"))
    )
    (net (code "106") (name "unconnected-(U$8-0-Pad15)") (class "Default")
      (node (ref "U$8") (pin "15") (pinfunction "0_15") (pintype "bidirectional"))
    )
    (net (code "107") (name "unconnected-(U$8-1-Pad16)") (class "Default")
      (node (ref "U$8") (pin "16") (pinfunction "1_16") (pintype "bidirectional"))
    )
    (net (code "108") (name "unconnected-(U$8-3V-Pad3)") (class "Default")
      (node (ref "U$8") (pin "3") (pinfunction "3V_3") (pintype "bidirectional"))
    )
    (net (code "109") (name "unconnected-(U$8-A0-Pad9)") (class "Default")
      (node (ref "U$8") (pin "9") (pinfunction "A0_9") (pintype "bidirectional"))
    )
    (net (code "110") (name "unconnected-(U$8-A1-Pad10)") (class "Default")
      (node (ref "U$8") (pin "10") (pinfunction "A1_10") (pintype "bidirectional"))
    )
    (net (code "111") (name "unconnected-(U$8-A2-Pad11)") (class "Default")
      (node (ref "U$8") (pin "11") (pinfunction "A2_11") (pintype "bidirectional"))
    )
    (net (code "112") (name "unconnected-(U$8-A3-Pad12)") (class "Default")
      (node (ref "U$8") (pin "12") (pinfunction "A3_12") (pintype "bidirectional"))
    )
    (net (code "113") (name "unconnected-(U$8-A4-Pad13)") (class "Default")
      (node (ref "U$8") (pin "13") (pinfunction "A4_13") (pintype "bidirectional"))
    )
    (net (code "114") (name "unconnected-(U$8-A5-Pad14)") (class "Default")
      (node (ref "U$8") (pin "14") (pinfunction "A5_14") (pintype "bidirectional"))
    )
    (net (code "115") (name "unconnected-(U$8-AREF-Pad8)") (class "Default")
      (node (ref "U$8") (pin "8") (pinfunction "AREF_8") (pintype "bidirectional"))
    )
    (net (code "116") (name "unconnected-(U$8-RST-Pad2)") (class "Default")
      (node (ref "U$8") (pin "2") (pinfunction "RST_2") (pintype "bidirectional"))
    )
    (net (code "117") (name "unconnected-(U$8-USB-Pad1)") (class "Default")
      (node (ref "U$8") (pin "1") (pinfunction "USB_1") (pintype "bidirectional"))
    )
    (net (code "118") (name "unconnected-(U$8-VIN-Pad7)") (class "Default")
      (node (ref "U$8") (pin "7") (pinfunction "VIN_7") (pintype "bidirectional"))
    )
  )
)
